# DE-120824_01.net
KiCad netlist of a schematic drawn in Altium Designer
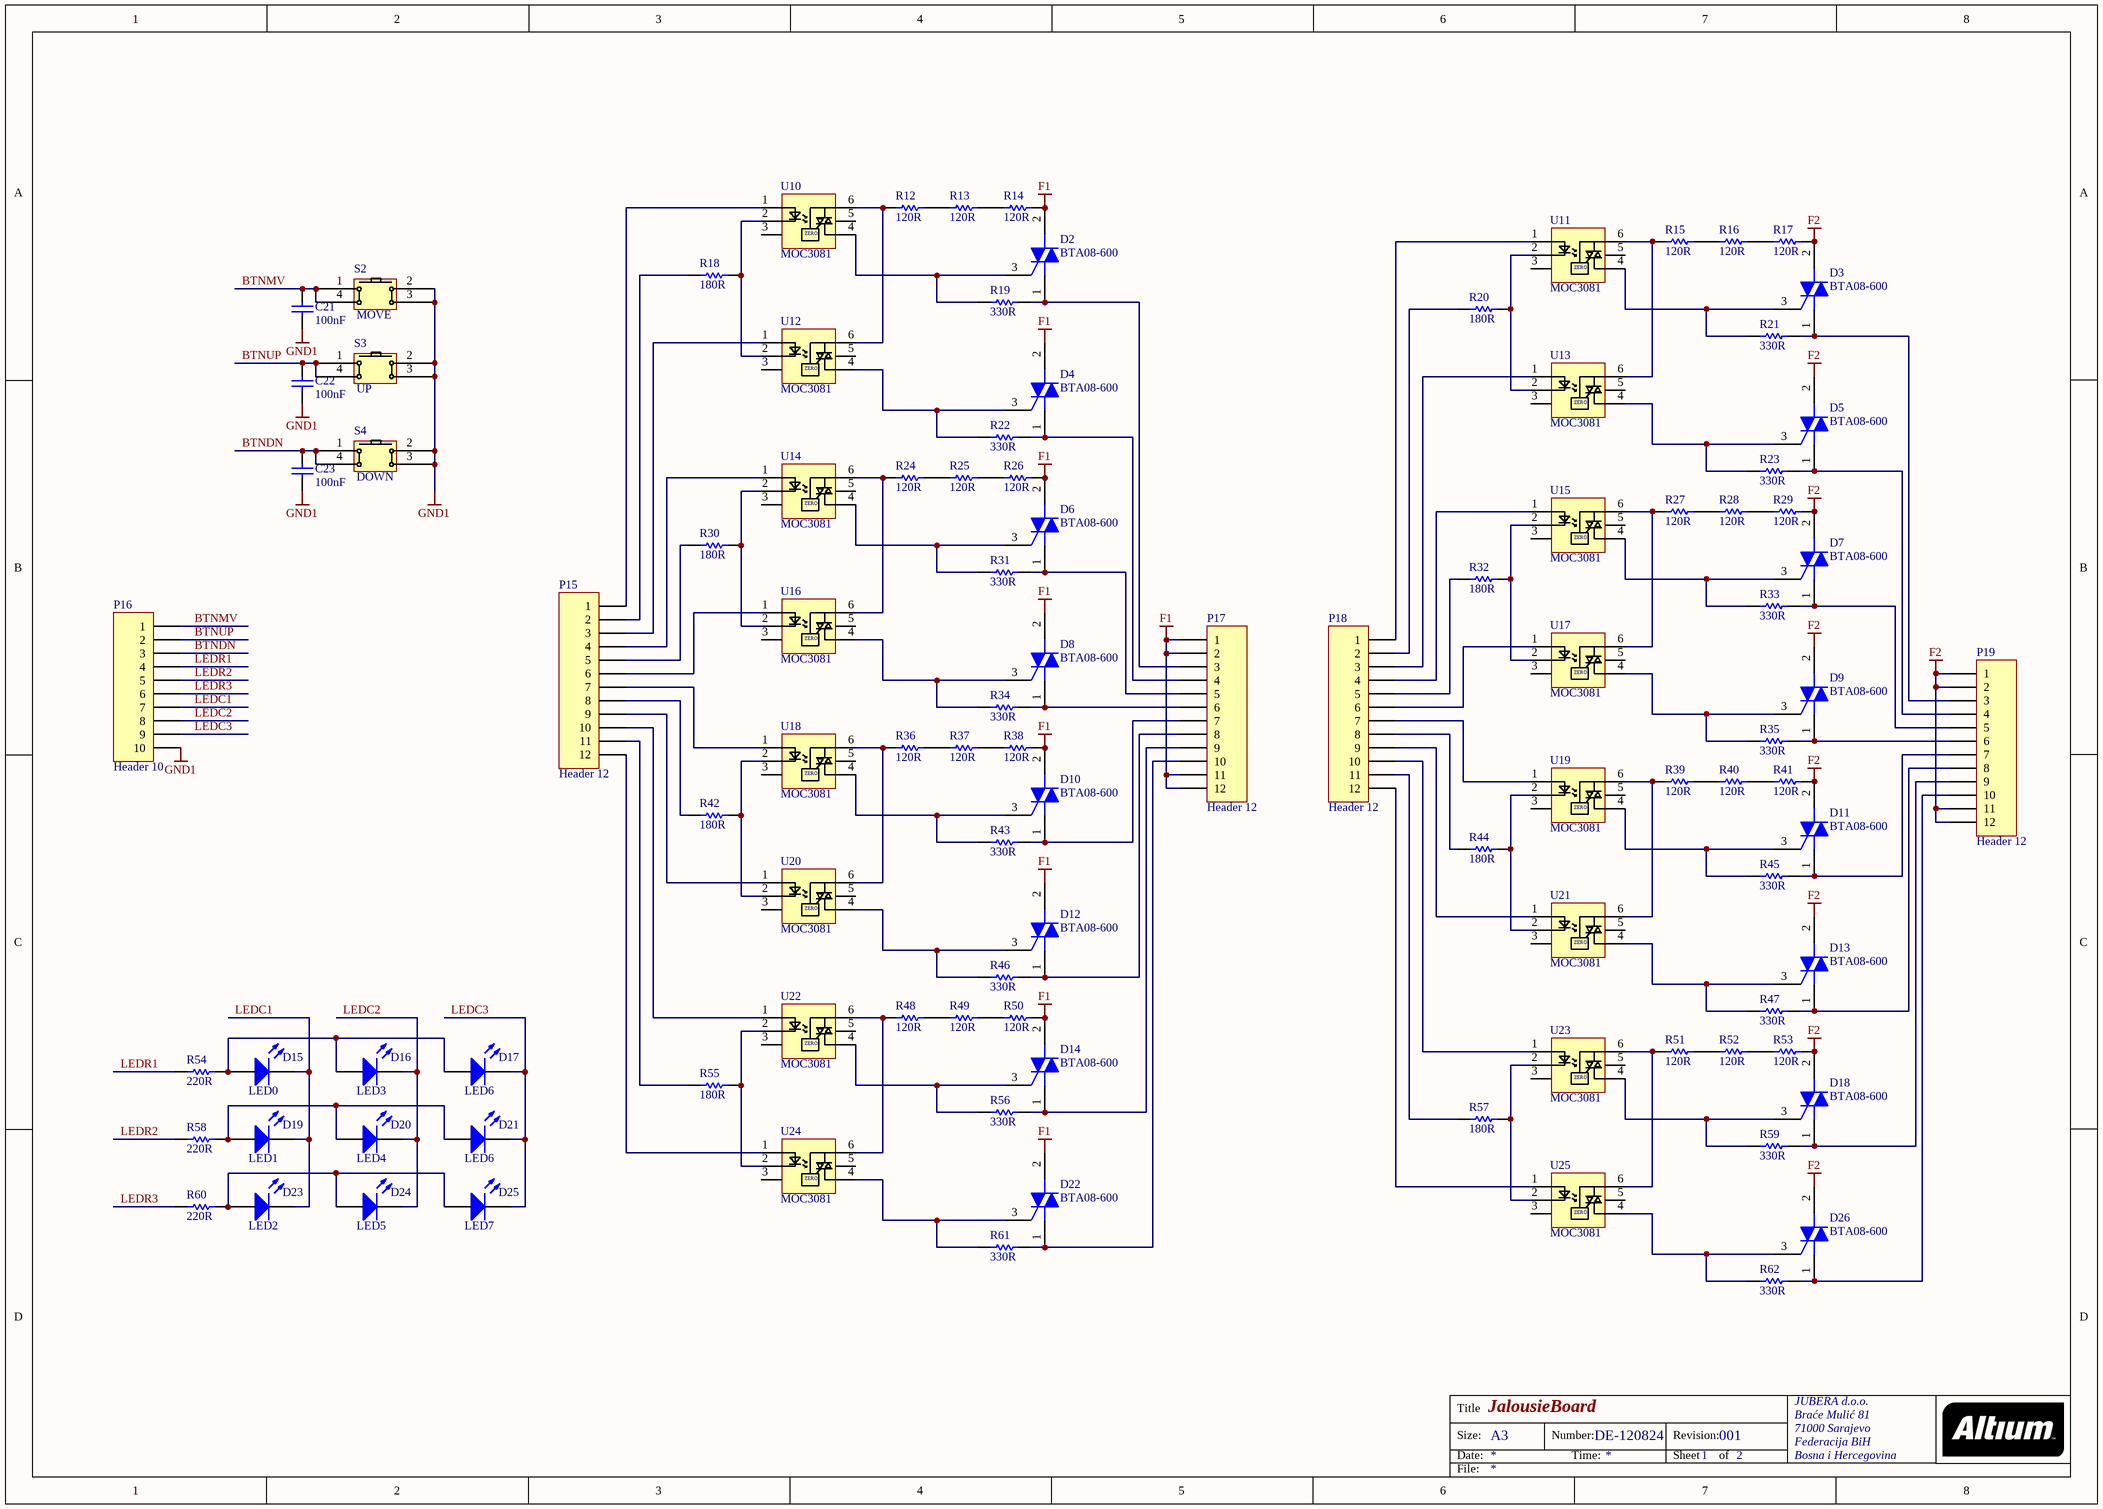
[diagram p0: DE-120824_01.SchDoc]

(export (version "E")
  (design (tool "Eeschema 10.0.6"))
  (components
    (comp (ref "C21")
      (value "100nF")
      (footprint "0603")
      (description "Ceramic Chip Capacitor - Standard")
      (fields (field (name "Comment") "C0603") (field (name "PUBLISHER") "Altium Limited"))
      (libsource (lib "DE-120824") (part "C0603"))
    )
    (comp (ref "C22")
      (value "100nF")
      (footprint "0603")
      (description "Ceramic Chip Capacitor - Standard")
      (fields (field (name "Comment") "C0603") (field (name "PUBLISHER") "Altium Limited"))
      (libsource (lib "DE-120824") (part "C0603"))
    )
    (comp (ref "C23")
      (value "100nF")
      (footprint "0603")
      (description "Ceramic Chip Capacitor - Standard")
      (fields (field (name "Comment") "C0603") (field (name "PUBLISHER") "Altium Limited"))
      (libsource (lib "DE-120824") (part "C0603"))
    )
    (comp (ref "D2")
      (value "BTA08-600")
      (footprint "ONSC-TO-220-3-221A-07")
      (description "Triacs, Silicon Bidirectional Thyristor, 3-Pin TO-220, Pb-Free, Tube")
      (fields (field (name "MANUFACTURER") "On Semiconductor") (field (name "PARTNUMBER") "BTA08-600BW3G"))
      (libsource (lib "DE-120824") (part "BTA08-600BW3G"))
    )
    (comp (ref "D3")
      (value "BTA08-600")
      (footprint "ONSC-TO-220-3-221A-07")
      (description "Triacs, Silicon Bidirectional Thyristor, 3-Pin TO-220, Pb-Free, Tube")
      (fields (field (name "MANUFACTURER") "On Semiconductor") (field (name "PARTNUMBER") "BTA08-600BW3G"))
      (libsource (lib "DE-120824") (part "BTA08-600BW3G"))
    )
    (comp (ref "D4")
      (value "BTA08-600")
      (footprint "ONSC-TO-220-3-221A-07")
      (description "Triacs, Silicon Bidirectional Thyristor, 3-Pin TO-220, Pb-Free, Tube")
      (fields (field (name "MANUFACTURER") "On Semiconductor") (field (name "PARTNUMBER") "BTA08-600BW3G"))
      (libsource (lib "DE-120824") (part "BTA08-600BW3G"))
    )
    (comp (ref "D5")
      (value "BTA08-600")
      (footprint "ONSC-TO-220-3-221A-07")
      (description "Triacs, Silicon Bidirectional Thyristor, 3-Pin TO-220, Pb-Free, Tube")
      (fields (field (name "MANUFACTURER") "On Semiconductor") (field (name "PARTNUMBER") "BTA08-600BW3G"))
      (libsource (lib "DE-120824") (part "BTA08-600BW3G"))
    )
    (comp (ref "D6")
      (value "BTA08-600")
      (footprint "ONSC-TO-220-3-221A-07")
      (description "Triacs, Silicon Bidirectional Thyristor, 3-Pin TO-220, Pb-Free, Tube")
      (fields (field (name "MANUFACTURER") "On Semiconductor") (field (name "PARTNUMBER") "BTA08-600BW3G"))
      (libsource (lib "DE-120824") (part "BTA08-600BW3G"))
    )
    (comp (ref "D7")
      (value "BTA08-600")
      (footprint "ONSC-TO-220-3-221A-07")
      (description "Triacs, Silicon Bidirectional Thyristor, 3-Pin TO-220, Pb-Free, Tube")
      (fields (field (name "MANUFACTURER") "On Semiconductor") (field (name "PARTNUMBER") "BTA08-600BW3G"))
      (libsource (lib "DE-120824") (part "BTA08-600BW3G"))
    )
    (comp (ref "D8")
      (value "BTA08-600")
      (footprint "ONSC-TO-220-3-221A-07")
      (description "Triacs, Silicon Bidirectional Thyristor, 3-Pin TO-220, Pb-Free, Tube")
      (fields (field (name "MANUFACTURER") "On Semiconductor") (field (name "PARTNUMBER") "BTA08-600BW3G"))
      (libsource (lib "DE-120824") (part "BTA08-600BW3G"))
    )
    (comp (ref "D9")
      (value "BTA08-600")
      (footprint "ONSC-TO-220-3-221A-07")
      (description "Triacs, Silicon Bidirectional Thyristor, 3-Pin TO-220, Pb-Free, Tube")
      (fields (field (name "MANUFACTURER") "On Semiconductor") (field (name "PARTNUMBER") "BTA08-600BW3G"))
      (libsource (lib "DE-120824") (part "BTA08-600BW3G"))
    )
    (comp (ref "D10")
      (value "BTA08-600")
      (footprint "ONSC-TO-220-3-221A-07")
      (description "Triacs, Silicon Bidirectional Thyristor, 3-Pin TO-220, Pb-Free, Tube")
      (fields (field (name "MANUFACTURER") "On Semiconductor") (field (name "PARTNUMBER") "BTA08-600BW3G"))
      (libsource (lib "DE-120824") (part "BTA08-600BW3G"))
    )
    (comp (ref "D11")
      (value "BTA08-600")
      (footprint "ONSC-TO-220-3-221A-07")
      (description "Triacs, Silicon Bidirectional Thyristor, 3-Pin TO-220, Pb-Free, Tube")
      (fields (field (name "MANUFACTURER") "On Semiconductor") (field (name "PARTNUMBER") "BTA08-600BW3G"))
      (libsource (lib "DE-120824") (part "BTA08-600BW3G"))
    )
    (comp (ref "D12")
      (value "BTA08-600")
      (footprint "ONSC-TO-220-3-221A-07")
      (description "Triacs, Silicon Bidirectional Thyristor, 3-Pin TO-220, Pb-Free, Tube")
      (fields (field (name "MANUFACTURER") "On Semiconductor") (field (name "PARTNUMBER") "BTA08-600BW3G"))
      (libsource (lib "DE-120824") (part "BTA08-600BW3G"))
    )
    (comp (ref "D13")
      (value "BTA08-600")
      (footprint "ONSC-TO-220-3-221A-07")
      (description "Triacs, Silicon Bidirectional Thyristor, 3-Pin TO-220, Pb-Free, Tube")
      (fields (field (name "MANUFACTURER") "On Semiconductor") (field (name "PARTNUMBER") "BTA08-600BW3G"))
      (libsource (lib "DE-120824") (part "BTA08-600BW3G"))
    )
    (comp (ref "D14")
      (value "BTA08-600")
      (footprint "ONSC-TO-220-3-221A-07")
      (description "Triacs, Silicon Bidirectional Thyristor, 3-Pin TO-220, Pb-Free, Tube")
      (fields (field (name "MANUFACTURER") "On Semiconductor") (field (name "PARTNUMBER") "BTA08-600BW3G"))
      (libsource (lib "DE-120824") (part "BTA08-600BW3G"))
    )
    (comp (ref "D15")
      (value "LED0")
      (footprint "1.6X0.8X0.8")
      (description "Blue Surface Mount Chip LED, Blue")
      (fields (field (name "PUBLISHER") "Altium Limited"))
      (libsource (lib "DE-120824") (part "HSMB-C190"))
    )
    (comp (ref "D16")
      (value "LED3")
      (footprint "1.6X0.8X0.8")
      (description "Blue Surface Mount Chip LED, Blue")
      (fields (field (name "PUBLISHER") "Altium Limited"))
      (libsource (lib "DE-120824") (part "HSMB-C190"))
    )
    (comp (ref "D17")
      (value "LED6")
      (footprint "1.6X0.8X0.8")
      (description "Blue Surface Mount Chip LED, Blue")
      (fields (field (name "PUBLISHER") "Altium Limited"))
      (libsource (lib "DE-120824") (part "HSMB-C190"))
    )
    (comp (ref "D18")
      (value "BTA08-600")
      (footprint "ONSC-TO-220-3-221A-07")
      (description "Triacs, Silicon Bidirectional Thyristor, 3-Pin TO-220, Pb-Free, Tube")
      (fields (field (name "MANUFACTURER") "On Semiconductor") (field (name "PARTNUMBER") "BTA08-600BW3G"))
      (libsource (lib "DE-120824") (part "BTA08-600BW3G"))
    )
    (comp (ref "D19")
      (value "LED1")
      (footprint "1.6X0.8X0.8")
      (description "Blue Surface Mount Chip LED, Blue")
      (fields (field (name "PUBLISHER") "Altium Limited"))
      (libsource (lib "DE-120824") (part "HSMB-C190"))
    )
    (comp (ref "D20")
      (value "LED4")
      (footprint "1.6X0.8X0.8")
      (description "Blue Surface Mount Chip LED, Blue")
      (fields (field (name "PUBLISHER") "Altium Limited"))
      (libsource (lib "DE-120824") (part "HSMB-C190"))
    )
    (comp (ref "D21")
      (value "LED6")
      (footprint "1.6X0.8X0.8")
      (description "Blue Surface Mount Chip LED, Blue")
      (fields (field (name "PUBLISHER") "Altium Limited"))
      (libsource (lib "DE-120824") (part "HSMB-C190"))
    )
    (comp (ref "D22")
      (value "BTA08-600")
      (footprint "ONSC-TO-220-3-221A-07")
      (description "Triacs, Silicon Bidirectional Thyristor, 3-Pin TO-220, Pb-Free, Tube")
      (fields (field (name "MANUFACTURER") "On Semiconductor") (field (name "PARTNUMBER") "BTA08-600BW3G"))
      (libsource (lib "DE-120824") (part "BTA08-600BW3G"))
    )
    (comp (ref "D23")
      (value "LED2")
      (footprint "1.6X0.8X0.8")
      (description "Blue Surface Mount Chip LED, Blue")
      (fields (field (name "PUBLISHER") "Altium Limited"))
      (libsource (lib "DE-120824") (part "HSMB-C190"))
    )
    (comp (ref "D24")
      (value "LED5")
      (footprint "1.6X0.8X0.8")
      (description "Blue Surface Mount Chip LED, Blue")
      (fields (field (name "PUBLISHER") "Altium Limited"))
      (libsource (lib "DE-120824") (part "HSMB-C190"))
    )
    (comp (ref "D25")
      (value "LED7")
      (footprint "1.6X0.8X0.8")
      (description "Blue Surface Mount Chip LED, Blue")
      (fields (field (name "PUBLISHER") "Altium Limited"))
      (libsource (lib "DE-120824") (part "HSMB-C190"))
    )
    (comp (ref "D26")
      (value "BTA08-600")
      (footprint "ONSC-TO-220-3-221A-07")
      (description "Triacs, Silicon Bidirectional Thyristor, 3-Pin TO-220, Pb-Free, Tube")
      (fields (field (name "MANUFACTURER") "On Semiconductor") (field (name "PARTNUMBER") "BTA08-600BW3G"))
      (libsource (lib "DE-120824") (part "BTA08-600BW3G"))
    )
    (comp (ref "P15")
      (value "Header 12")
      (footprint "HDR1X12")
      (description "Header, 12-Pin")
      (fields (field (name "PUBLISHER") "Altium Limited"))
      (libsource (lib "") (part "Header 12_1"))
    )
    (comp (ref "P16")
      (value "Header 10")
      (footprint "HDR1X10")
      (description "Header, 10-Pin")
      (fields (field (name "PUBLISHER") "Altium Limited"))
      (libsource (lib "Miscellaneous Connectors") (part "Header 10"))
    )
    (comp (ref "P17")
      (value "Header 12")
      (footprint "HDR1X12")
      (description "Header, 12-Pin")
      (fields (field (name "PUBLISHER") "Altium Limited"))
      (libsource (lib "Miscellaneous Connectors") (part "Header 12"))
    )
    (comp (ref "P18")
      (value "Header 12")
      (footprint "HDR1X12")
      (description "Header, 12-Pin")
      (fields (field (name "PUBLISHER") "Altium Limited"))
      (libsource (lib "") (part "Header 12_1"))
    )
    (comp (ref "P19")
      (value "Header 12")
      (footprint "HDR1X12")
      (description "Header, 12-Pin")
      (fields (field (name "PUBLISHER") "Altium Limited"))
      (libsource (lib "Miscellaneous Connectors") (part "Header 12"))
    )
    (comp (ref "R12")
      (value "120R")
      (footprint "ERA-0805")
      (fields (field (name "PUBLISHER") "Altium Limited"))
      (libsource (lib "DE-120824") (part "ERAS"))
    )
    (comp (ref "R13")
      (value "120R")
      (footprint "ERA-0805")
      (fields (field (name "PUBLISHER") "Altium Limited"))
      (libsource (lib "DE-120824") (part "ERAS"))
    )
    (comp (ref "R14")
      (value "120R")
      (footprint "ERA-0805")
      (fields (field (name "PUBLISHER") "Altium Limited"))
      (libsource (lib "DE-120824") (part "ERAS"))
    )
    (comp (ref "R15")
      (value "120R")
      (footprint "ERA-0805")
      (fields (field (name "PUBLISHER") "Altium Limited"))
      (libsource (lib "DE-120824") (part "ERAS"))
    )
    (comp (ref "R16")
      (value "120R")
      (footprint "ERA-0805")
      (fields (field (name "PUBLISHER") "Altium Limited"))
      (libsource (lib "DE-120824") (part "ERAS"))
    )
    (comp (ref "R17")
      (value "120R")
      (footprint "ERA-0805")
      (fields (field (name "PUBLISHER") "Altium Limited"))
      (libsource (lib "DE-120824") (part "ERAS"))
    )
    (comp (ref "R18")
      (value "180R")
      (footprint "ERA-0603")
      (fields (field (name "PUBLISHER") "Altium Limited"))
      (libsource (lib "DE-120824") (part "ERA3Y"))
    )
    (comp (ref "R19")
      (value "330R")
      (footprint "ERA-0805")
      (fields (field (name "PUBLISHER") "Altium Limited"))
      (libsource (lib "DE-120824") (part "ERAS"))
    )
    (comp (ref "R20")
      (value "180R")
      (footprint "ERA-0603")
      (fields (field (name "PUBLISHER") "Altium Limited"))
      (libsource (lib "DE-120824") (part "ERA3Y"))
    )
    (comp (ref "R21")
      (value "330R")
      (footprint "ERA-0805")
      (fields (field (name "PUBLISHER") "Altium Limited"))
      (libsource (lib "DE-120824") (part "ERAS"))
    )
    (comp (ref "R22")
      (value "330R")
      (footprint "ERA-0805")
      (fields (field (name "PUBLISHER") "Altium Limited"))
      (libsource (lib "DE-120824") (part "ERAS"))
    )
    (comp (ref "R23")
      (value "330R")
      (footprint "ERA-0805")
      (fields (field (name "PUBLISHER") "Altium Limited"))
      (libsource (lib "DE-120824") (part "ERAS"))
    )
    (comp (ref "R24")
      (value "120R")
      (footprint "ERA-0805")
      (fields (field (name "PUBLISHER") "Altium Limited"))
      (libsource (lib "DE-120824") (part "ERAS"))
    )
    (comp (ref "R25")
      (value "120R")
      (footprint "ERA-0805")
      (fields (field (name "PUBLISHER") "Altium Limited"))
      (libsource (lib "DE-120824") (part "ERAS"))
    )
    (comp (ref "R26")
      (value "120R")
      (footprint "ERA-0805")
      (fields (field (name "PUBLISHER") "Altium Limited"))
      (libsource (lib "DE-120824") (part "ERAS"))
    )
    (comp (ref "R27")
      (value "120R")
      (footprint "ERA-0805")
      (fields (field (name "PUBLISHER") "Altium Limited"))
      (libsource (lib "DE-120824") (part "ERAS"))
    )
    (comp (ref "R28")
      (value "120R")
      (footprint "ERA-0805")
      (fields (field (name "PUBLISHER") "Altium Limited"))
      (libsource (lib "DE-120824") (part "ERAS"))
    )
    (comp (ref "R29")
      (value "120R")
      (footprint "ERA-0805")
      (fields (field (name "PUBLISHER") "Altium Limited"))
      (libsource (lib "DE-120824") (part "ERAS"))
    )
    (comp (ref "R30")
      (value "180R")
      (footprint "ERA-0603")
      (fields (field (name "PUBLISHER") "Altium Limited"))
      (libsource (lib "DE-120824") (part "ERA3Y"))
    )
    (comp (ref "R31")
      (value "330R")
      (footprint "ERA-0805")
      (fields (field (name "PUBLISHER") "Altium Limited"))
      (libsource (lib "DE-120824") (part "ERAS"))
    )
    (comp (ref "R32")
      (value "180R")
      (footprint "ERA-0603")
      (fields (field (name "PUBLISHER") "Altium Limited"))
      (libsource (lib "DE-120824") (part "ERA3Y"))
    )
    (comp (ref "R33")
      (value "330R")
      (footprint "ERA-0805")
      (fields (field (name "PUBLISHER") "Altium Limited"))
      (libsource (lib "DE-120824") (part "ERAS"))
    )
    (comp (ref "R34")
      (value "330R")
      (footprint "ERA-0805")
      (fields (field (name "PUBLISHER") "Altium Limited"))
      (libsource (lib "DE-120824") (part "ERAS"))
    )
    (comp (ref "R35")
      (value "330R")
      (footprint "ERA-0805")
      (fields (field (name "PUBLISHER") "Altium Limited"))
      (libsource (lib "DE-120824") (part "ERAS"))
    )
    (comp (ref "R36")
      (value "120R")
      (footprint "ERA-0805")
      (fields (field (name "PUBLISHER") "Altium Limited"))
      (libsource (lib "DE-120824") (part "ERAS"))
    )
    (comp (ref "R37")
      (value "120R")
      (footprint "ERA-0805")
      (fields (field (name "PUBLISHER") "Altium Limited"))
      (libsource (lib "DE-120824") (part "ERAS"))
    )
    (comp (ref "R38")
      (value "120R")
      (footprint "ERA-0805")
      (fields (field (name "PUBLISHER") "Altium Limited"))
      (libsource (lib "DE-120824") (part "ERAS"))
    )
    (comp (ref "R39")
      (value "120R")
      (footprint "ERA-0805")
      (fields (field (name "PUBLISHER") "Altium Limited"))
      (libsource (lib "DE-120824") (part "ERAS"))
    )
    (comp (ref "R40")
      (value "120R")
      (footprint "ERA-0805")
      (fields (field (name "PUBLISHER") "Altium Limited"))
      (libsource (lib "DE-120824") (part "ERAS"))
    )
    (comp (ref "R41")
      (value "120R")
      (footprint "ERA-0805")
      (fields (field (name "PUBLISHER") "Altium Limited"))
      (libsource (lib "DE-120824") (part "ERAS"))
    )
    (comp (ref "R42")
      (value "180R")
      (footprint "ERA-0603")
      (fields (field (name "PUBLISHER") "Altium Limited"))
      (libsource (lib "DE-120824") (part "ERA3Y"))
    )
    (comp (ref "R43")
      (value "330R")
      (footprint "ERA-0805")
      (fields (field (name "PUBLISHER") "Altium Limited"))
      (libsource (lib "DE-120824") (part "ERAS"))
    )
    (comp (ref "R44")
      (value "180R")
      (footprint "ERA-0603")
      (fields (field (name "PUBLISHER") "Altium Limited"))
      (libsource (lib "DE-120824") (part "ERA3Y"))
    )
    (comp (ref "R45")
      (value "330R")
      (footprint "ERA-0805")
      (fields (field (name "PUBLISHER") "Altium Limited"))
      (libsource (lib "DE-120824") (part "ERAS"))
    )
    (comp (ref "R46")
      (value "330R")
      (footprint "ERA-0805")
      (fields (field (name "PUBLISHER") "Altium Limited"))
      (libsource (lib "DE-120824") (part "ERAS"))
    )
    (comp (ref "R47")
      (value "330R")
      (footprint "ERA-0805")
      (fields (field (name "PUBLISHER") "Altium Limited"))
      (libsource (lib "DE-120824") (part "ERAS"))
    )
    (comp (ref "R48")
      (value "120R")
      (footprint "ERA-0805")
      (fields (field (name "PUBLISHER") "Altium Limited"))
      (libsource (lib "DE-120824") (part "ERAS"))
    )
    (comp (ref "R49")
      (value "120R")
      (footprint "ERA-0805")
      (fields (field (name "PUBLISHER") "Altium Limited"))
      (libsource (lib "DE-120824") (part "ERAS"))
    )
    (comp (ref "R50")
      (value "120R")
      (footprint "ERA-0805")
      (fields (field (name "PUBLISHER") "Altium Limited"))
      (libsource (lib "DE-120824") (part "ERAS"))
    )
    (comp (ref "R51")
      (value "120R")
      (footprint "ERA-0805")
      (fields (field (name "PUBLISHER") "Altium Limited"))
      (libsource (lib "DE-120824") (part "ERAS"))
    )
    (comp (ref "R52")
      (value "120R")
      (footprint "ERA-0805")
      (fields (field (name "PUBLISHER") "Altium Limited"))
      (libsource (lib "DE-120824") (part "ERAS"))
    )
    (comp (ref "R53")
      (value "120R")
      (footprint "ERA-0805")
      (fields (field (name "PUBLISHER") "Altium Limited"))
      (libsource (lib "DE-120824") (part "ERAS"))
    )
    (comp (ref "R54")
      (value "220R")
      (footprint "ERA-0805")
      (fields (field (name "PUBLISHER") "Altium Limited"))
      (libsource (lib "DE-120824") (part "ERAS"))
    )
    (comp (ref "R55")
      (value "180R")
      (footprint "ERA-0603")
      (fields (field (name "PUBLISHER") "Altium Limited"))
      (libsource (lib "DE-120824") (part "ERA3Y"))
    )
    (comp (ref "R56")
      (value "330R")
      (footprint "ERA-0805")
      (fields (field (name "PUBLISHER") "Altium Limited"))
      (libsource (lib "DE-120824") (part "ERAS"))
    )
    (comp (ref "R57")
      (value "180R")
      (footprint "ERA-0603")
      (fields (field (name "PUBLISHER") "Altium Limited"))
      (libsource (lib "DE-120824") (part "ERA3Y"))
    )
    (comp (ref "R58")
      (value "220R")
      (footprint "ERA-0805")
      (fields (field (name "PUBLISHER") "Altium Limited"))
      (libsource (lib "DE-120824") (part "ERAS"))
    )
    (comp (ref "R59")
      (value "330R")
      (footprint "ERA-0805")
      (fields (field (name "PUBLISHER") "Altium Limited"))
      (libsource (lib "DE-120824") (part "ERAS"))
    )
    (comp (ref "R60")
      (value "220R")
      (footprint "ERA-0805")
      (fields (field (name "PUBLISHER") "Altium Limited"))
      (libsource (lib "DE-120824") (part "ERAS"))
    )
    (comp (ref "R61")
      (value "330R")
      (footprint "ERA-0805")
      (fields (field (name "PUBLISHER") "Altium Limited"))
      (libsource (lib "DE-120824") (part "ERAS"))
    )
    (comp (ref "R62")
      (value "330R")
      (footprint "ERA-0805")
      (fields (field (name "PUBLISHER") "Altium Limited"))
      (libsource (lib "DE-120824") (part "ERAS"))
    )
    (comp (ref "S2")
      (value "MOVE")
      (footprint "TACTILE_SWITCH")
      (libsource (lib "DE-120824") (part "TACKTILE_SWITCH"))
    )
    (comp (ref "S3")
      (value "UP")
      (footprint "TACTILE_SWITCH")
      (libsource (lib "DE-120824") (part "TACKTILE_SWITCH"))
    )
    (comp (ref "S4")
      (value "DOWN")
      (footprint "TACTILE_SWITCH")
      (libsource (lib "DE-120824") (part "TACKTILE_SWITCH"))
    )
    (comp (ref "U10")
      (value "MOC3081")
      (footprint "DIP6")
      (description "Zero-Cross Optoisolator Triac Driver")
      (libsource (lib "DE-120824") (part "MOC3081"))
    )
    (comp (ref "U11")
      (value "MOC3081")
      (footprint "DIP6")
      (description "Zero-Cross Optoisolator Triac Driver")
      (libsource (lib "DE-120824") (part "MOC3081"))
    )
    (comp (ref "U12")
      (value "MOC3081")
      (footprint "DIP6")
      (description "Zero-Cross Optoisolator Triac Driver")
      (libsource (lib "DE-120824") (part "MOC3081"))
    )
    (comp (ref "U13")
      (value "MOC3081")
      (footprint "DIP6")
      (description "Zero-Cross Optoisolator Triac Driver")
      (libsource (lib "DE-120824") (part "MOC3081"))
    )
    (comp (ref "U14")
      (value "MOC3081")
      (footprint "DIP6")
      (description "Zero-Cross Optoisolator Triac Driver")
      (libsource (lib "DE-120824") (part "MOC3081"))
    )
    (comp (ref "U15")
      (value "MOC3081")
      (footprint "DIP6")
      (description "Zero-Cross Optoisolator Triac Driver")
      (libsource (lib "DE-120824") (part "MOC3081"))
    )
    (comp (ref "U16")
      (value "MOC3081")
      (footprint "DIP6")
      (description "Zero-Cross Optoisolator Triac Driver")
      (libsource (lib "DE-120824") (part "MOC3081"))
    )
    (comp (ref "U17")
      (value "MOC3081")
      (footprint "DIP6")
      (description "Zero-Cross Optoisolator Triac Driver")
      (libsource (lib "DE-120824") (part "MOC3081"))
    )
    (comp (ref "U18")
      (value "MOC3081")
      (footprint "DIP6")
      (description "Zero-Cross Optoisolator Triac Driver")
      (libsource (lib "DE-120824") (part "MOC3081"))
    )
    (comp (ref "U19")
      (value "MOC3081")
      (footprint "DIP6")
      (description "Zero-Cross Optoisolator Triac Driver")
      (libsource (lib "DE-120824") (part "MOC3081"))
    )
    (comp (ref "U20")
      (value "MOC3081")
      (footprint "DIP6")
      (description "Zero-Cross Optoisolator Triac Driver")
      (libsource (lib "DE-120824") (part "MOC3081"))
    )
    (comp (ref "U21")
      (value "MOC3081")
      (footprint "DIP6")
      (description "Zero-Cross Optoisolator Triac Driver")
      (libsource (lib "DE-120824") (part "MOC3081"))
    )
    (comp (ref "U22")
      (value "MOC3081")
      (footprint "DIP6")
      (description "Zero-Cross Optoisolator Triac Driver")
      (libsource (lib "DE-120824") (part "MOC3081"))
    )
    (comp (ref "U23")
      (value "MOC3081")
      (footprint "DIP6")
      (description "Zero-Cross Optoisolator Triac Driver")
      (libsource (lib "DE-120824") (part "MOC3081"))
    )
    (comp (ref "U24")
      (value "MOC3081")
      (footprint "DIP6")
      (description "Zero-Cross Optoisolator Triac Driver")
      (libsource (lib "DE-120824") (part "MOC3081"))
    )
    (comp (ref "U25")
      (value "MOC3081")
      (footprint "DIP6")
      (description "Zero-Cross Optoisolator Triac Driver")
      (libsource (lib "DE-120824") (part "MOC3081"))
    )
  )
  (nets
    (net (code "1") (name "/BTNDN") (class "Default")
      (node (ref "C23") (pin "1") (pinfunction "1_1") (pintype "passive"))
      (node (ref "P16") (pin "3") (pinfunction "3_3") (pintype "passive"))
      (node (ref "S4") (pin "1") (pinfunction "1_1") (pintype "passive"))
      (node (ref "S4") (pin "4") (pinfunction "4_4") (pintype "passive"))
    )
    (net (code "2") (name "/BTNMV") (class "Default")
      (node (ref "C21") (pin "1") (pinfunction "1_1") (pintype "passive"))
      (node (ref "P16") (pin "1") (pinfunction "1_1") (pintype "passive"))
      (node (ref "S2") (pin "1") (pinfunction "1_1") (pintype "passive"))
      (node (ref "S2") (pin "4") (pinfunction "4_4") (pintype "passive"))
    )
    (net (code "3") (name "/BTNUP") (class "Default")
      (node (ref "C22") (pin "1") (pinfunction "1_1") (pintype "passive"))
      (node (ref "P16") (pin "2") (pinfunction "2_2") (pintype "passive"))
      (node (ref "S3") (pin "1") (pinfunction "1_1") (pintype "passive"))
      (node (ref "S3") (pin "4") (pinfunction "4_4") (pintype "passive"))
    )
    (net (code "4") (name "/LEDC1") (class "Default")
      (node (ref "D15") (pin "2") (pinfunction "K_2") (pintype "passive"))
      (node (ref "D19") (pin "2") (pinfunction "K_2") (pintype "passive"))
      (node (ref "D23") (pin "2") (pinfunction "K_2") (pintype "passive"))
      (node (ref "P16") (pin "7") (pinfunction "7_7") (pintype "passive"))
    )
    (net (code "5") (name "/LEDC2") (class "Default")
      (node (ref "D16") (pin "2") (pinfunction "K_2") (pintype "passive"))
      (node (ref "D20") (pin "2") (pinfunction "K_2") (pintype "passive"))
      (node (ref "D24") (pin "2") (pinfunction "K_2") (pintype "passive"))
      (node (ref "P16") (pin "8") (pinfunction "8_8") (pintype "passive"))
    )
    (net (code "6") (name "/LEDC3") (class "Default")
      (node (ref "D17") (pin "2") (pinfunction "K_2") (pintype "passive"))
      (node (ref "D21") (pin "2") (pinfunction "K_2") (pintype "passive"))
      (node (ref "D25") (pin "2") (pinfunction "K_2") (pintype "passive"))
      (node (ref "P16") (pin "9") (pinfunction "9_9") (pintype "passive"))
    )
    (net (code "7") (name "/LEDR1") (class "Default")
      (node (ref "P16") (pin "4") (pinfunction "4_4") (pintype "passive"))
      (node (ref "R54") (pin "1") (pinfunction "1_1") (pintype "passive"))
    )
    (net (code "8") (name "/LEDR2") (class "Default")
      (node (ref "P16") (pin "5") (pinfunction "5_5") (pintype "passive"))
      (node (ref "R58") (pin "1") (pinfunction "1_1") (pintype "passive"))
    )
    (net (code "9") (name "/LEDR3") (class "Default")
      (node (ref "P16") (pin "6") (pinfunction "6_6") (pintype "passive"))
      (node (ref "R60") (pin "1") (pinfunction "1_1") (pintype "passive"))
    )
    (net (code "10") (name "F1") (class "Default")
      (node (ref "D10") (pin "2") (pinfunction "MT2_2") (pintype "passive"))
      (node (ref "D12") (pin "2") (pinfunction "MT2_2") (pintype "passive"))
      (node (ref "D14") (pin "2") (pinfunction "MT2_2") (pintype "passive"))
      (node (ref "D2") (pin "2") (pinfunction "MT2_2") (pintype "passive"))
      (node (ref "D22") (pin "2") (pinfunction "MT2_2") (pintype "passive"))
      (node (ref "D4") (pin "2") (pinfunction "MT2_2") (pintype "passive"))
      (node (ref "D6") (pin "2") (pinfunction "MT2_2") (pintype "passive"))
      (node (ref "D8") (pin "2") (pinfunction "MT2_2") (pintype "passive"))
      (node (ref "P17") (pin "1") (pinfunction "1_1") (pintype "passive"))
      (node (ref "P17") (pin "11") (pinfunction "11_11") (pintype "passive"))
      (node (ref "P17") (pin "12") (pinfunction "12_12") (pintype "passive"))
      (node (ref "P17") (pin "2") (pinfunction "2_2") (pintype "passive"))
      (node (ref "R14") (pin "2") (pinfunction "2_2") (pintype "passive"))
      (node (ref "R26") (pin "2") (pinfunction "2_2") (pintype "passive"))
      (node (ref "R38") (pin "2") (pinfunction "2_2") (pintype "passive"))
      (node (ref "R50") (pin "2") (pinfunction "2_2") (pintype "passive"))
    )
    (net (code "11") (name "F2") (class "Default")
      (node (ref "D11") (pin "2") (pinfunction "MT2_2") (pintype "passive"))
      (node (ref "D13") (pin "2") (pinfunction "MT2_2") (pintype "passive"))
      (node (ref "D18") (pin "2") (pinfunction "MT2_2") (pintype "passive"))
      (node (ref "D26") (pin "2") (pinfunction "MT2_2") (pintype "passive"))
      (node (ref "D3") (pin "2") (pinfunction "MT2_2") (pintype "passive"))
      (node (ref "D5") (pin "2") (pinfunction "MT2_2") (pintype "passive"))
      (node (ref "D7") (pin "2") (pinfunction "MT2_2") (pintype "passive"))
      (node (ref "D9") (pin "2") (pinfunction "MT2_2") (pintype "passive"))
      (node (ref "P19") (pin "1") (pinfunction "1_1") (pintype "passive"))
      (node (ref "P19") (pin "11") (pinfunction "11_11") (pintype "passive"))
      (node (ref "P19") (pin "12") (pinfunction "12_12") (pintype "passive"))
      (node (ref "P19") (pin "2") (pinfunction "2_2") (pintype "passive"))
      (node (ref "R17") (pin "2") (pinfunction "2_2") (pintype "passive"))
      (node (ref "R29") (pin "2") (pinfunction "2_2") (pintype "passive"))
      (node (ref "R41") (pin "2") (pinfunction "2_2") (pintype "passive"))
      (node (ref "R53") (pin "2") (pinfunction "2_2") (pintype "passive"))
    )
    (net (code "12") (name "GND1") (class "Default")
      (node (ref "C21") (pin "2") (pinfunction "2_2") (pintype "passive"))
      (node (ref "C22") (pin "2") (pinfunction "2_2") (pintype "passive"))
      (node (ref "C23") (pin "2") (pinfunction "2_2") (pintype "passive"))
      (node (ref "P16") (pin "10") (pinfunction "10_10") (pintype "passive"))
      (node (ref "S2") (pin "2") (pinfunction "2_2") (pintype "passive"))
      (node (ref "S2") (pin "3") (pinfunction "3_3") (pintype "passive"))
      (node (ref "S3") (pin "2") (pinfunction "2_2") (pintype "passive"))
      (node (ref "S3") (pin "3") (pinfunction "3_3") (pintype "passive"))
      (node (ref "S4") (pin "2") (pinfunction "2_2") (pintype "passive"))
      (node (ref "S4") (pin "3") (pinfunction "3_3") (pintype "passive"))
    )
    (net (code "13") (name "Net-(D2-G)") (class "Default")
      (node (ref "D2") (pin "3") (pinfunction "G_3") (pintype "passive"))
      (node (ref "R19") (pin "1") (pinfunction "1_1") (pintype "passive"))
      (node (ref "U10") (pin "4") (pinfunction "4_4") (pintype "passive"))
    )
    (net (code "14") (name "Net-(D2-MT1)") (class "Default")
      (node (ref "D2") (pin "1") (pinfunction "MT1_1") (pintype "passive"))
      (node (ref "P17") (pin "3") (pinfunction "3_3") (pintype "passive"))
      (node (ref "R19") (pin "2") (pinfunction "2_2") (pintype "passive"))
    )
    (net (code "15") (name "Net-(D3-G)") (class "Default")
      (node (ref "D3") (pin "3") (pinfunction "G_3") (pintype "passive"))
      (node (ref "R21") (pin "1") (pinfunction "1_1") (pintype "passive"))
      (node (ref "U11") (pin "4") (pinfunction "4_4") (pintype "passive"))
    )
    (net (code "16") (name "Net-(D3-MT1)") (class "Default")
      (node (ref "D3") (pin "1") (pinfunction "MT1_1") (pintype "passive"))
      (node (ref "P19") (pin "3") (pinfunction "3_3") (pintype "passive"))
      (node (ref "R21") (pin "2") (pinfunction "2_2") (pintype "passive"))
    )
    (net (code "17") (name "Net-(D4-G)") (class "Default")
      (node (ref "D4") (pin "3") (pinfunction "G_3") (pintype "passive"))
      (node (ref "R22") (pin "1") (pinfunction "1_1") (pintype "passive"))
      (node (ref "U12") (pin "4") (pinfunction "4_4") (pintype "passive"))
    )
    (net (code "18") (name "Net-(D4-MT1)") (class "Default")
      (node (ref "D4") (pin "1") (pinfunction "MT1_1") (pintype "passive"))
      (node (ref "P17") (pin "4") (pinfunction "4_4") (pintype "passive"))
      (node (ref "R22") (pin "2") (pinfunction "2_2") (pintype "passive"))
    )
    (net (code "19") (name "Net-(D5-G)") (class "Default")
      (node (ref "D5") (pin "3") (pinfunction "G_3") (pintype "passive"))
      (node (ref "R23") (pin "1") (pinfunction "1_1") (pintype "passive"))
      (node (ref "U13") (pin "4") (pinfunction "4_4") (pintype "passive"))
    )
    (net (code "20") (name "Net-(D5-MT1)") (class "Default")
      (node (ref "D5") (pin "1") (pinfunction "MT1_1") (pintype "passive"))
      (node (ref "P19") (pin "4") (pinfunction "4_4") (pintype "passive"))
      (node (ref "R23") (pin "2") (pinfunction "2_2") (pintype "passive"))
    )
    (net (code "21") (name "Net-(D6-G)") (class "Default")
      (node (ref "D6") (pin "3") (pinfunction "G_3") (pintype "passive"))
      (node (ref "R31") (pin "1") (pinfunction "1_1") (pintype "passive"))
      (node (ref "U14") (pin "4") (pinfunction "4_4") (pintype "passive"))
    )
    (net (code "22") (name "Net-(D6-MT1)") (class "Default")
      (node (ref "D6") (pin "1") (pinfunction "MT1_1") (pintype "passive"))
      (node (ref "P17") (pin "5") (pinfunction "5_5") (pintype "passive"))
      (node (ref "R31") (pin "2") (pinfunction "2_2") (pintype "passive"))
    )
    (net (code "23") (name "Net-(D7-G)") (class "Default")
      (node (ref "D7") (pin "3") (pinfunction "G_3") (pintype "passive"))
      (node (ref "R33") (pin "1") (pinfunction "1_1") (pintype "passive"))
      (node (ref "U15") (pin "4") (pinfunction "4_4") (pintype "passive"))
    )
    (net (code "24") (name "Net-(D7-MT1)") (class "Default")
      (node (ref "D7") (pin "1") (pinfunction "MT1_1") (pintype "passive"))
      (node (ref "P19") (pin "5") (pinfunction "5_5") (pintype "passive"))
      (node (ref "R33") (pin "2") (pinfunction "2_2") (pintype "passive"))
    )
    (net (code "25") (name "Net-(D8-G)") (class "Default")
      (node (ref "D8") (pin "3") (pinfunction "G_3") (pintype "passive"))
      (node (ref "R34") (pin "1") (pinfunction "1_1") (pintype "passive"))
      (node (ref "U16") (pin "4") (pinfunction "4_4") (pintype "passive"))
    )
    (net (code "26") (name "Net-(D8-MT1)") (class "Default")
      (node (ref "D8") (pin "1") (pinfunction "MT1_1") (pintype "passive"))
      (node (ref "P17") (pin "6") (pinfunction "6_6") (pintype "passive"))
      (node (ref "R34") (pin "2") (pinfunction "2_2") (pintype "passive"))
    )
    (net (code "27") (name "Net-(D9-G)") (class "Default")
      (node (ref "D9") (pin "3") (pinfunction "G_3") (pintype "passive"))
      (node (ref "R35") (pin "1") (pinfunction "1_1") (pintype "passive"))
      (node (ref "U17") (pin "4") (pinfunction "4_4") (pintype "passive"))
    )
    (net (code "28") (name "Net-(D9-MT1)") (class "Default")
      (node (ref "D9") (pin "1") (pinfunction "MT1_1") (pintype "passive"))
      (node (ref "P19") (pin "6") (pinfunction "6_6") (pintype "passive"))
      (node (ref "R35") (pin "2") (pinfunction "2_2") (pintype "passive"))
    )
    (net (code "29") (name "Net-(D10-G)") (class "Default")
      (node (ref "D10") (pin "3") (pinfunction "G_3") (pintype "passive"))
      (node (ref "R43") (pin "1") (pinfunction "1_1") (pintype "passive"))
      (node (ref "U18") (pin "4") (pinfunction "4_4") (pintype "passive"))
    )
    (net (code "30") (name "Net-(D10-MT1)") (class "Default")
      (node (ref "D10") (pin "1") (pinfunction "MT1_1") (pintype "passive"))
      (node (ref "P17") (pin "7") (pinfunction "7_7") (pintype "passive"))
      (node (ref "R43") (pin "2") (pinfunction "2_2") (pintype "passive"))
    )
    (net (code "31") (name "Net-(D11-G)") (class "Default")
      (node (ref "D11") (pin "3") (pinfunction "G_3") (pintype "passive"))
      (node (ref "R45") (pin "1") (pinfunction "1_1") (pintype "passive"))
      (node (ref "U19") (pin "4") (pinfunction "4_4") (pintype "passive"))
    )
    (net (code "32") (name "Net-(D11-MT1)") (class "Default")
      (node (ref "D11") (pin "1") (pinfunction "MT1_1") (pintype "passive"))
      (node (ref "P19") (pin "7") (pinfunction "7_7") (pintype "passive"))
      (node (ref "R45") (pin "2") (pinfunction "2_2") (pintype "passive"))
    )
    (net (code "33") (name "Net-(D12-G)") (class "Default")
      (node (ref "D12") (pin "3") (pinfunction "G_3") (pintype "passive"))
      (node (ref "R46") (pin "1") (pinfunction "1_1") (pintype "passive"))
      (node (ref "U20") (pin "4") (pinfunction "4_4") (pintype "passive"))
    )
    (net (code "34") (name "Net-(D12-MT1)") (class "Default")
      (node (ref "D12") (pin "1") (pinfunction "MT1_1") (pintype "passive"))
      (node (ref "P17") (pin "8") (pinfunction "8_8") (pintype "passive"))
      (node (ref "R46") (pin "2") (pinfunction "2_2") (pintype "passive"))
    )
    (net (code "35") (name "Net-(D13-G)") (class "Default")
      (node (ref "D13") (pin "3") (pinfunction "G_3") (pintype "passive"))
      (node (ref "R47") (pin "1") (pinfunction "1_1") (pintype "passive"))
      (node (ref "U21") (pin "4") (pinfunction "4_4") (pintype "passive"))
    )
    (net (code "36") (name "Net-(D13-MT1)") (class "Default")
      (node (ref "D13") (pin "1") (pinfunction "MT1_1") (pintype "passive"))
      (node (ref "P19") (pin "8") (pinfunction "8_8") (pintype "passive"))
      (node (ref "R47") (pin "2") (pinfunction "2_2") (pintype "passive"))
    )
    (net (code "37") (name "Net-(D14-G)") (class "Default")
      (node (ref "D14") (pin "3") (pinfunction "G_3") (pintype "passive"))
      (node (ref "R56") (pin "1") (pinfunction "1_1") (pintype "passive"))
      (node (ref "U22") (pin "4") (pinfunction "4_4") (pintype "passive"))
    )
    (net (code "38") (name "Net-(D14-MT1)") (class "Default")
      (node (ref "D14") (pin "1") (pinfunction "MT1_1") (pintype "passive"))
      (node (ref "P17") (pin "9") (pinfunction "9_9") (pintype "passive"))
      (node (ref "R56") (pin "2") (pinfunction "2_2") (pintype "passive"))
    )
    (net (code "39") (name "Net-(D15-A)") (class "Default")
      (node (ref "D15") (pin "1") (pinfunction "A_1") (pintype "passive"))
      (node (ref "D16") (pin "1") (pinfunction "A_1") (pintype "passive"))
      (node (ref "D17") (pin "1") (pinfunction "A_1") (pintype "passive"))
      (node (ref "R54") (pin "2") (pinfunction "2_2") (pintype "passive"))
    )
    (net (code "40") (name "Net-(D18-G)") (class "Default")
      (node (ref "D18") (pin "3") (pinfunction "G_3") (pintype "passive"))
      (node (ref "R59") (pin "1") (pinfunction "1_1") (pintype "passive"))
      (node (ref "U23") (pin "4") (pinfunction "4_4") (pintype "passive"))
    )
    (net (code "41") (name "Net-(D18-MT1)") (class "Default")
      (node (ref "D18") (pin "1") (pinfunction "MT1_1") (pintype "passive"))
      (node (ref "P19") (pin "9") (pinfunction "9_9") (pintype "passive"))
      (node (ref "R59") (pin "2") (pinfunction "2_2") (pintype "passive"))
    )
    (net (code "42") (name "Net-(D19-A)") (class "Default")
      (node (ref "D19") (pin "1") (pinfunction "A_1") (pintype "passive"))
      (node (ref "D20") (pin "1") (pinfunction "A_1") (pintype "passive"))
      (node (ref "D21") (pin "1") (pinfunction "A_1") (pintype "passive"))
      (node (ref "R58") (pin "2") (pinfunction "2_2") (pintype "passive"))
    )
    (net (code "43") (name "Net-(D22-G)") (class "Default")
      (node (ref "D22") (pin "3") (pinfunction "G_3") (pintype "passive"))
      (node (ref "R61") (pin "1") (pinfunction "1_1") (pintype "passive"))
      (node (ref "U24") (pin "4") (pinfunction "4_4") (pintype "passive"))
    )
    (net (code "44") (name "Net-(D22-MT1)") (class "Default")
      (node (ref "D22") (pin "1") (pinfunction "MT1_1") (pintype "passive"))
      (node (ref "P17") (pin "10") (pinfunction "10_10") (pintype "passive"))
      (node (ref "R61") (pin "2") (pinfunction "2_2") (pintype "passive"))
    )
    (net (code "45") (name "Net-(D23-A)") (class "Default")
      (node (ref "D23") (pin "1") (pinfunction "A_1") (pintype "passive"))
      (node (ref "D24") (pin "1") (pinfunction "A_1") (pintype "passive"))
      (node (ref "D25") (pin "1") (pinfunction "A_1") (pintype "passive"))
      (node (ref "R60") (pin "2") (pinfunction "2_2") (pintype "passive"))
    )
    (net (code "46") (name "Net-(D26-G)") (class "Default")
      (node (ref "D26") (pin "3") (pinfunction "G_3") (pintype "passive"))
      (node (ref "R62") (pin "1") (pinfunction "1_1") (pintype "passive"))
      (node (ref "U25") (pin "4") (pinfunction "4_4") (pintype "passive"))
    )
    (net (code "47") (name "Net-(D26-MT1)") (class "Default")
      (node (ref "D26") (pin "1") (pinfunction "MT1_1") (pintype "passive"))
      (node (ref "P19") (pin "10") (pinfunction "10_10") (pintype "passive"))
      (node (ref "R62") (pin "2") (pinfunction "2_2") (pintype "passive"))
    )
    (net (code "48") (name "Net-(P15-Pad1)") (class "Default")
      (node (ref "P15") (pin "1") (pinfunction "1_1") (pintype "passive"))
      (node (ref "U10") (pin "1") (pinfunction "1_1") (pintype "passive"))
    )
    (net (code "49") (name "Net-(P15-Pad2)") (class "Default")
      (node (ref "P15") (pin "2") (pinfunction "2_2") (pintype "passive"))
      (node (ref "R18") (pin "1") (pinfunction "1_1") (pintype "passive"))
    )
    (net (code "50") (name "Net-(P15-Pad3)") (class "Default")
      (node (ref "P15") (pin "3") (pinfunction "3_3") (pintype "passive"))
      (node (ref "U12") (pin "1") (pinfunction "1_1") (pintype "passive"))
    )
    (net (code "51") (name "Net-(P15-Pad4)") (class "Default")
      (node (ref "P15") (pin "4") (pinfunction "4_4") (pintype "passive"))
      (node (ref "U14") (pin "1") (pinfunction "1_1") (pintype "passive"))
    )
    (net (code "52") (name "Net-(P15-Pad5)") (class "Default")
      (node (ref "P15") (pin "5") (pinfunction "5_5") (pintype "passive"))
      (node (ref "R30") (pin "1") (pinfunction "1_1") (pintype "passive"))
    )
    (net (code "53") (name "Net-(P15-Pad6)") (class "Default")
      (node (ref "P15") (pin "6") (pinfunction "6_6") (pintype "passive"))
      (node (ref "U16") (pin "1") (pinfunction "1_1") (pintype "passive"))
    )
    (net (code "54") (name "Net-(P15-Pad7)") (class "Default")
      (node (ref "P15") (pin "7") (pinfunction "7_7") (pintype "passive"))
      (node (ref "U18") (pin "1") (pinfunction "1_1") (pintype "passive"))
    )
    (net (code "55") (name "Net-(P15-Pad8)") (class "Default")
      (node (ref "P15") (pin "8") (pinfunction "8_8") (pintype "passive"))
      (node (ref "R42") (pin "1") (pinfunction "1_1") (pintype "passive"))
    )
    (net (code "56") (name "Net-(P15-Pad9)") (class "Default")
      (node (ref "P15") (pin "9") (pinfunction "9_9") (pintype "passive"))
      (node (ref "U20") (pin "1") (pinfunction "1_1") (pintype "passive"))
    )
    (net (code "57") (name "Net-(P15-Pad10)") (class "Default")
      (node (ref "P15") (pin "10") (pinfunction "10_10") (pintype "passive"))
      (node (ref "U22") (pin "1") (pinfunction "1_1") (pintype "passive"))
    )
    (net (code "58") (name "Net-(P15-Pad11)") (class "Default")
      (node (ref "P15") (pin "11") (pinfunction "11_11") (pintype "passive"))
      (node (ref "R55") (pin "1") (pinfunction "1_1") (pintype "passive"))
    )
    (net (code "59") (name "Net-(P15-Pad12)") (class "Default")
      (node (ref "P15") (pin "12") (pinfunction "12_12") (pintype "passive"))
      (node (ref "U24") (pin "1") (pinfunction "1_1") (pintype "passive"))
    )
    (net (code "60") (name "Net-(P18-Pad1)") (class "Default")
      (node (ref "P18") (pin "1") (pinfunction "1_1") (pintype "passive"))
      (node (ref "U11") (pin "1") (pinfunction "1_1") (pintype "passive"))
    )
    (net (code "61") (name "Net-(P18-Pad2)") (class "Default")
      (node (ref "P18") (pin "2") (pinfunction "2_2") (pintype "passive"))
      (node (ref "R20") (pin "1") (pinfunction "1_1") (pintype "passive"))
    )
    (net (code "62") (name "Net-(P18-Pad3)") (class "Default")
      (node (ref "P18") (pin "3") (pinfunction "3_3") (pintype "passive"))
      (node (ref "U13") (pin "1") (pinfunction "1_1") (pintype "passive"))
    )
    (net (code "63") (name "Net-(P18-Pad4)") (class "Default")
      (node (ref "P18") (pin "4") (pinfunction "4_4") (pintype "passive"))
      (node (ref "U15") (pin "1") (pinfunction "1_1") (pintype "passive"))
    )
    (net (code "64") (name "Net-(P18-Pad5)") (class "Default")
      (node (ref "P18") (pin "5") (pinfunction "5_5") (pintype "passive"))
      (node (ref "R32") (pin "1") (pinfunction "1_1") (pintype "passive"))
    )
    (net (code "65") (name "Net-(P18-Pad6)") (class "Default")
      (node (ref "P18") (pin "6") (pinfunction "6_6") (pintype "passive"))
      (node (ref "U17") (pin "1") (pinfunction "1_1") (pintype "passive"))
    )
    (net (code "66") (name "Net-(P18-Pad7)") (class "Default")
      (node (ref "P18") (pin "7") (pinfunction "7_7") (pintype "passive"))
      (node (ref "U19") (pin "1") (pinfunction "1_1") (pintype "passive"))
    )
    (net (code "67") (name "Net-(P18-Pad8)") (class "Default")
      (node (ref "P18") (pin "8") (pinfunction "8_8") (pintype "passive"))
      (node (ref "R44") (pin "1") (pinfunction "1_1") (pintype "passive"))
    )
    (net (code "68") (name "Net-(P18-Pad9)") (class "Default")
      (node (ref "P18") (pin "9") (pinfunction "9_9") (pintype "passive"))
      (node (ref "U21") (pin "1") (pinfunction "1_1") (pintype "passive"))
    )
    (net (code "69") (name "Net-(P18-Pad10)") (class "Default")
      (node (ref "P18") (pin "10") (pinfunction "10_10") (pintype "passive"))
      (node (ref "U23") (pin "1") (pinfunction "1_1") (pintype "passive"))
    )
    (net (code "70") (name "Net-(P18-Pad11)") (class "Default")
      (node (ref "P18") (pin "11") (pinfunction "11_11") (pintype "passive"))
      (node (ref "R57") (pin "1") (pinfunction "1_1") (pintype "passive"))
    )
    (net (code "71") (name "Net-(P18-Pad12)") (class "Default")
      (node (ref "P18") (pin "12") (pinfunction "12_12") (pintype "passive"))
      (node (ref "U25") (pin "1") (pinfunction "1_1") (pintype "passive"))
    )
    (net (code "72") (name "Net-(R12-Pad1)") (class "Default")
      (node (ref "R12") (pin "1") (pinfunction "1_1") (pintype "passive"))
      (node (ref "U10") (pin "6") (pinfunction "6_6") (pintype "passive"))
      (node (ref "U12") (pin "6") (pinfunction "6_6") (pintype "passive"))
    )
    (net (code "73") (name "Net-(R12-Pad2)") (class "Default")
      (node (ref "R12") (pin "2") (pinfunction "2_2") (pintype "passive"))
      (node (ref "R13") (pin "1") (pinfunction "1_1") (pintype "passive"))
    )
    (net (code "74") (name "Net-(R13-Pad2)") (class "Default")
      (node (ref "R13") (pin "2") (pinfunction "2_2") (pintype "passive"))
      (node (ref "R14") (pin "1") (pinfunction "1_1") (pintype "passive"))
    )
    (net (code "75") (name "Net-(R15-Pad1)") (class "Default")
      (node (ref "R15") (pin "1") (pinfunction "1_1") (pintype "passive"))
      (node (ref "U11") (pin "6") (pinfunction "6_6") (pintype "passive"))
      (node (ref "U13") (pin "6") (pinfunction "6_6") (pintype "passive"))
    )
    (net (code "76") (name "Net-(R15-Pad2)") (class "Default")
      (node (ref "R15") (pin "2") (pinfunction "2_2") (pintype "passive"))
      (node (ref "R16") (pin "1") (pinfunction "1_1") (pintype "passive"))
    )
    (net (code "77") (name "Net-(R16-Pad2)") (class "Default")
      (node (ref "R16") (pin "2") (pinfunction "2_2") (pintype "passive"))
      (node (ref "R17") (pin "1") (pinfunction "1_1") (pintype "passive"))
    )
    (net (code "78") (name "Net-(R18-Pad2)") (class "Default")
      (node (ref "R18") (pin "2") (pinfunction "2_2") (pintype "passive"))
      (node (ref "U10") (pin "2") (pinfunction "2_2") (pintype "passive"))
      (node (ref "U12") (pin "2") (pinfunction "2_2") (pintype "passive"))
    )
    (net (code "79") (name "Net-(R20-Pad2)") (class "Default")
      (node (ref "R20") (pin "2") (pinfunction "2_2") (pintype "passive"))
      (node (ref "U11") (pin "2") (pinfunction "2_2") (pintype "passive"))
      (node (ref "U13") (pin "2") (pinfunction "2_2") (pintype "passive"))
    )
    (net (code "80") (name "Net-(R24-Pad1)") (class "Default")
      (node (ref "R24") (pin "1") (pinfunction "1_1") (pintype "passive"))
      (node (ref "U14") (pin "6") (pinfunction "6_6") (pintype "passive"))
      (node (ref "U16") (pin "6") (pinfunction "6_6") (pintype "passive"))
    )
    (net (code "81") (name "Net-(R24-Pad2)") (class "Default")
      (node (ref "R24") (pin "2") (pinfunction "2_2") (pintype "passive"))
      (node (ref "R25") (pin "1") (pinfunction "1_1") (pintype "passive"))
    )
    (net (code "82") (name "Net-(R25-Pad2)") (class "Default")
      (node (ref "R25") (pin "2") (pinfunction "2_2") (pintype "passive"))
      (node (ref "R26") (pin "1") (pinfunction "1_1") (pintype "passive"))
    )
    (net (code "83") (name "Net-(R27-Pad1)") (class "Default")
      (node (ref "R27") (pin "1") (pinfunction "1_1") (pintype "passive"))
      (node (ref "U15") (pin "6") (pinfunction "6_6") (pintype "passive"))
      (node (ref "U17") (pin "6") (pinfunction "6_6") (pintype "passive"))
    )
    (net (code "84") (name "Net-(R27-Pad2)") (class "Default")
      (node (ref "R27") (pin "2") (pinfunction "2_2") (pintype "passive"))
      (node (ref "R28") (pin "1") (pinfunction "1_1") (pintype "passive"))
    )
    (net (code "85") (name "Net-(R28-Pad2)") (class "Default")
      (node (ref "R28") (pin "2") (pinfunction "2_2") (pintype "passive"))
      (node (ref "R29") (pin "1") (pinfunction "1_1") (pintype "passive"))
    )
    (net (code "86") (name "Net-(R30-Pad2)") (class "Default")
      (node (ref "R30") (pin "2") (pinfunction "2_2") (pintype "passive"))
      (node (ref "U14") (pin "2") (pinfunction "2_2") (pintype "passive"))
      (node (ref "U16") (pin "2") (pinfunction "2_2") (pintype "passive"))
    )
    (net (code "87") (name "Net-(R32-Pad2)") (class "Default")
      (node (ref "R32") (pin "2") (pinfunction "2_2") (pintype "passive"))
      (node (ref "U15") (pin "2") (pinfunction "2_2") (pintype "passive"))
      (node (ref "U17") (pin "2") (pinfunction "2_2") (pintype "passive"))
    )
    (net (code "88") (name "Net-(R36-Pad1)") (class "Default")
      (node (ref "R36") (pin "1") (pinfunction "1_1") (pintype "passive"))
      (node (ref "U18") (pin "6") (pinfunction "6_6") (pintype "passive"))
      (node (ref "U20") (pin "6") (pinfunction "6_6") (pintype "passive"))
    )
    (net (code "89") (name "Net-(R36-Pad2)") (class "Default")
      (node (ref "R36") (pin "2") (pinfunction "2_2") (pintype "passive"))
      (node (ref "R37") (pin "1") (pinfunction "1_1") (pintype "passive"))
    )
    (net (code "90") (name "Net-(R37-Pad2)") (class "Default")
      (node (ref "R37") (pin "2") (pinfunction "2_2") (pintype "passive"))
      (node (ref "R38") (pin "1") (pinfunction "1_1") (pintype "passive"))
    )
    (net (code "91") (name "Net-(R39-Pad1)") (class "Default")
      (node (ref "R39") (pin "1") (pinfunction "1_1") (pintype "passive"))
      (node (ref "U19") (pin "6") (pinfunction "6_6") (pintype "passive"))
      (node (ref "U21") (pin "6") (pinfunction "6_6") (pintype "passive"))
    )
    (net (code "92") (name "Net-(R39-Pad2)") (class "Default")
      (node (ref "R39") (pin "2") (pinfunction "2_2") (pintype "passive"))
      (node (ref "R40") (pin "1") (pinfunction "1_1") (pintype "passive"))
    )
    (net (code "93") (name "Net-(R40-Pad2)") (class "Default")
      (node (ref "R40") (pin "2") (pinfunction "2_2") (pintype "passive"))
      (node (ref "R41") (pin "1") (pinfunction "1_1") (pintype "passive"))
    )
    (net (code "94") (name "Net-(R42-Pad2)") (class "Default")
      (node (ref "R42") (pin "2") (pinfunction "2_2") (pintype "passive"))
      (node (ref "U18") (pin "2") (pinfunction "2_2") (pintype "passive"))
      (node (ref "U20") (pin "2") (pinfunction "2_2") (pintype "passive"))
    )
    (net (code "95") (name "Net-(R44-Pad2)") (class "Default")
      (node (ref "R44") (pin "2") (pinfunction "2_2") (pintype "passive"))
      (node (ref "U19") (pin "2") (pinfunction "2_2") (pintype "passive"))
      (node (ref "U21") (pin "2") (pinfunction "2_2") (pintype "passive"))
    )
    (net (code "96") (name "Net-(R48-Pad1)") (class "Default")
      (node (ref "R48") (pin "1") (pinfunction "1_1") (pintype "passive"))
      (node (ref "U22") (pin "6") (pinfunction "6_6") (pintype "passive"))
      (node (ref "U24") (pin "6") (pinfunction "6_6") (pintype "passive"))
    )
    (net (code "97") (name "Net-(R48-Pad2)") (class "Default")
      (node (ref "R48") (pin "2") (pinfunction "2_2") (pintype "passive"))
      (node (ref "R49") (pin "1") (pinfunction "1_1") (pintype "passive"))
    )
    (net (code "98") (name "Net-(R49-Pad2)") (class "Default")
      (node (ref "R49") (pin "2") (pinfunction "2_2") (pintype "passive"))
      (node (ref "R50") (pin "1") (pinfunction "1_1") (pintype "passive"))
    )
    (net (code "99") (name "Net-(R51-Pad1)") (class "Default")
      (node (ref "R51") (pin "1") (pinfunction "1_1") (pintype "passive"))
      (node (ref "U23") (pin "6") (pinfunction "6_6") (pintype "passive"))
      (node (ref "U25") (pin "6") (pinfunction "6_6") (pintype "passive"))
    )
    (net (code "100") (name "Net-(R51-Pad2)") (class "Default")
      (node (ref "R51") (pin "2") (pinfunction "2_2") (pintype "passive"))
      (node (ref "R52") (pin "1") (pinfunction "1_1") (pintype "passive"))
    )
    (net (code "101") (name "Net-(R52-Pad2)") (class "Default")
      (node (ref "R52") (pin "2") (pinfunction "2_2") (pintype "passive"))
      (node (ref "R53") (pin "1") (pinfunction "1_1") (pintype "passive"))
    )
    (net (code "102") (name "Net-(R55-Pad2)") (class "Default")
      (node (ref "R55") (pin "2") (pinfunction "2_2") (pintype "passive"))
      (node (ref "U22") (pin "2") (pinfunction "2_2") (pintype "passive"))
      (node (ref "U24") (pin "2") (pinfunction "2_2") (pintype "passive"))
    )
    (net (code "103") (name "Net-(R57-Pad2)") (class "Default")
      (node (ref "R57") (pin "2") (pinfunction "2_2") (pintype "passive"))
      (node (ref "U23") (pin "2") (pinfunction "2_2") (pintype "passive"))
      (node (ref "U25") (pin "2") (pinfunction "2_2") (pintype "passive"))
    )
    (net (code "104") (name "unconnected-(U10-Pad3)") (class "Default")
      (node (ref "U10") (pin "3") (pinfunction "3_3") (pintype "passive"))
    )
    (net (code "105") (name "unconnected-(U10-Pad5)") (class "Default")
      (node (ref "U10") (pin "5") (pinfunction "5_5") (pintype "passive"))
    )
    (net (code "106") (name "unconnected-(U11-Pad3)") (class "Default")
      (node (ref "U11") (pin "3") (pinfunction "3_3") (pintype "passive"))
    )
    (net (code "107") (name "unconnected-(U11-Pad5)") (class "Default")
      (node (ref "U11") (pin "5") (pinfunction "5_5") (pintype "passive"))
    )
    (net (code "108") (name "unconnected-(U12-Pad3)") (class "Default")
      (node (ref "U12") (pin "3") (pinfunction "3_3") (pintype "passive"))
    )
    (net (code "109") (name "unconnected-(U12-Pad5)") (class "Default")
      (node (ref "U12") (pin "5") (pinfunction "5_5") (pintype "passive"))
    )
    (net (code "110") (name "unconnected-(U13-Pad3)") (class "Default")
      (node (ref "U13") (pin "3") (pinfunction "3_3") (pintype "passive"))
    )
    (net (code "111") (name "unconnected-(U13-Pad5)") (class "Default")
      (node (ref "U13") (pin "5") (pinfunction "5_5") (pintype "passive"))
    )
    (net (code "112") (name "unconnected-(U14-Pad3)") (class "Default")
      (node (ref "U14") (pin "3") (pinfunction "3_3") (pintype "passive"))
    )
    (net (code "113") (name "unconnected-(U14-Pad5)") (class "Default")
      (node (ref "U14") (pin "5") (pinfunction "5_5") (pintype "passive"))
    )
    (net (code "114") (name "unconnected-(U15-Pad3)") (class "Default")
      (node (ref "U15") (pin "3") (pinfunction "3_3") (pintype "passive"))
    )
    (net (code "115") (name "unconnected-(U15-Pad5)") (class "Default")
      (node (ref "U15") (pin "5") (pinfunction "5_5") (pintype "passive"))
    )
    (net (code "116") (name "unconnected-(U16-Pad3)") (class "Default")
      (node (ref "U16") (pin "3") (pinfunction "3_3") (pintype "passive"))
    )
    (net (code "117") (name "unconnected-(U16-Pad5)") (class "Default")
      (node (ref "U16") (pin "5") (pinfunction "5_5") (pintype "passive"))
    )
    (net (code "118") (name "unconnected-(U17-Pad3)") (class "Default")
      (node (ref "U17") (pin "3") (pinfunction "3_3") (pintype "passive"))
    )
    (net (code "119") (name "unconnected-(U17-Pad5)") (class "Default")
      (node (ref "U17") (pin "5") (pinfunction "5_5") (pintype "passive"))
    )
    (net (code "120") (name "unconnected-(U18-Pad3)") (class "Default")
      (node (ref "U18") (pin "3") (pinfunction "3_3") (pintype "passive"))
    )
    (net (code "121") (name "unconnected-(U18-Pad5)") (class "Default")
      (node (ref "U18") (pin "5") (pinfunction "5_5") (pintype "passive"))
    )
    (net (code "122") (name "unconnected-(U19-Pad3)") (class "Default")
      (node (ref "U19") (pin "3") (pinfunction "3_3") (pintype "passive"))
    )
    (net (code "123") (name "unconnected-(U19-Pad5)") (class "Default")
      (node (ref "U19") (pin "5") (pinfunction "5_5") (pintype "passive"))
    )
    (net (code "124") (name "unconnected-(U20-Pad3)") (class "Default")
      (node (ref "U20") (pin "3") (pinfunction "3_3") (pintype "passive"))
    )
    (net (code "125") (name "unconnected-(U20-Pad5)") (class "Default")
      (node (ref "U20") (pin "5") (pinfunction "5_5") (pintype "passive"))
    )
    (net (code "126") (name "unconnected-(U21-Pad3)") (class "Default")
      (node (ref "U21") (pin "3") (pinfunction "3_3") (pintype "passive"))
    )
    (net (code "127") (name "unconnected-(U21-Pad5)") (class "Default")
      (node (ref "U21") (pin "5") (pinfunction "5_5") (pintype "passive"))
    )
    (net (code "128") (name "unconnected-(U22-Pad3)") (class "Default")
      (node (ref "U22") (pin "3") (pinfunction "3_3") (pintype "passive"))
    )
    (net (code "129") (name "unconnected-(U22-Pad5)") (class "Default")
      (node (ref "U22") (pin "5") (pinfunction "5_5") (pintype "passive"))
    )
    (net (code "130") (name "unconnected-(U23-Pad3)") (class "Default")
      (node (ref "U23") (pin "3") (pinfunction "3_3") (pintype "passive"))
    )
    (net (code "131") (name "unconnected-(U23-Pad5)") (class "Default")
      (node (ref "U23") (pin "5") (pinfunction "5_5") (pintype "passive"))
    )
    (net (code "132") (name "unconnected-(U24-Pad3)") (class "Default")
      (node (ref "U24") (pin "3") (pinfunction "3_3") (pintype "passive"))
    )
    (net (code "133") (name "unconnected-(U24-Pad5)") (class "Default")
      (node (ref "U24") (pin "5") (pinfunction "5_5") (pintype "passive"))
    )
    (net (code "134") (name "unconnected-(U25-Pad3)") (class "Default")
      (node (ref "U25") (pin "3") (pinfunction "3_3") (pintype "passive"))
    )
    (net (code "135") (name "unconnected-(U25-Pad5)") (class "Default")
      (node (ref "U25") (pin "5") (pinfunction "5_5") (pintype "passive"))
    )
  )
)
